# max3051_breadboard.net
KiCad netlist of a schematic drawn in EAGLE
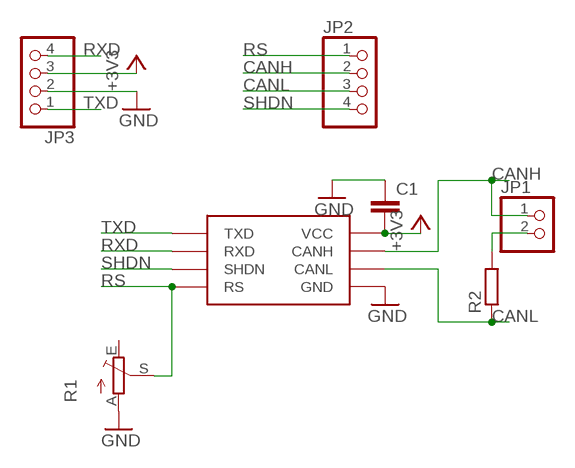
[diagram p0: schematic, sheet 1]

(export (version "E")
  (design (tool "Eeschema 10.0.6"))
  (components
    (comp (ref "C1")
      (value "C-EUC0603")
      (footprint "eagle-import:C0603")
      (libsource (lib "eagle-import") (part "C-EUC0603"))
    )
    (comp (ref "JP1")
      (value "PINHD-1X2")
      (footprint "eagle-import:1X02")
      (libsource (lib "eagle-import") (part "PINHD-1X2"))
    )
    (comp (ref "JP2")
      (value "PINHD-1X4")
      (footprint "eagle-import:1X04")
      (libsource (lib "eagle-import") (part "PINHD-1X4"))
    )
    (comp (ref "JP3")
      (value "PINHD-1X4")
      (footprint "eagle-import:1X04")
      (libsource (lib "eagle-import") (part "PINHD-1X4"))
    )
    (comp (ref "R1")
      (value "TRIM_EU-S64W")
      (footprint "eagle-import:S64W")
      (libsource (lib "eagle-import") (part "TRIM_EU-S64W"))
    )
    (comp (ref "R2")
      (value "R-EU_R0603")
      (footprint "eagle-import:R0603")
      (libsource (lib "eagle-import") (part "R-EU_R0603"))
    )
    (comp (ref "SOT1")
      (value "MAX3051ESA")
      (footprint "eagle-import:SO-08")
      (libsource (lib "eagle-import") (part "MAX3051ESA"))
    )
  )
  (nets
    (net (code "1") (name "+3V3") (class "Default")
      (node (ref "C1") (pin "2") (pinfunction "2_2") (pintype "passive"))
      (node (ref "JP3") (pin "3") (pinfunction "3_3") (pintype "passive"))
      (node (ref "SOT1") (pin "3") (pinfunction "VCC_3") (pintype "bidirectional"))
    )
    (net (code "2") (name "/CANH") (class "Default")
      (node (ref "JP1") (pin "1") (pinfunction "1_1") (pintype "passive"))
      (node (ref "JP2") (pin "2") (pinfunction "2_2") (pintype "passive"))
      (node (ref "SOT1") (pin "7") (pinfunction "CANH_7") (pintype "bidirectional"))
    )
    (net (code "3") (name "/CANL") (class "Default")
      (node (ref "JP2") (pin "3") (pinfunction "3_3") (pintype "passive"))
      (node (ref "R2") (pin "1") (pinfunction "1_1") (pintype "passive"))
      (node (ref "SOT1") (pin "6") (pinfunction "CANL_6") (pintype "bidirectional"))
    )
    (net (code "4") (name "/RS") (class "Default")
      (node (ref "JP2") (pin "1") (pinfunction "1_1") (pintype "passive"))
      (node (ref "R1") (pin "S") (pinfunction "S_S") (pintype "passive"))
      (node (ref "SOT1") (pin "8") (pinfunction "RS_8") (pintype "bidirectional"))
    )
    (net (code "5") (name "/RXD") (class "Default")
      (node (ref "JP3") (pin "4") (pinfunction "4_4") (pintype "passive"))
      (node (ref "SOT1") (pin "4") (pinfunction "RXD_4") (pintype "bidirectional"))
    )
    (net (code "6") (name "/SHDN") (class "Default")
      (node (ref "JP2") (pin "4") (pinfunction "4_4") (pintype "passive"))
      (node (ref "SOT1") (pin "5") (pinfunction "SHDN_5") (pintype "bidirectional"))
    )
    (net (code "7") (name "/TXD") (class "Default")
      (node (ref "JP3") (pin "1") (pinfunction "1_1") (pintype "passive"))
      (node (ref "SOT1") (pin "1") (pinfunction "TXD_1") (pintype "bidirectional"))
    )
    (net (code "8") (name "GND") (class "Default")
      (node (ref "C1") (pin "1") (pinfunction "1_1") (pintype "passive"))
      (node (ref "JP3") (pin "2") (pinfunction "2_2") (pintype "passive"))
      (node (ref "R1") (pin "A") (pinfunction "A_A") (pintype "passive"))
      (node (ref "SOT1") (pin "2") (pinfunction "GND_2") (pintype "bidirectional"))
    )
    (net (code "9") (name "Net-(JP1-Pad2)") (class "Default")
      (node (ref "JP1") (pin "2") (pinfunction "2_2") (pintype "passive"))
      (node (ref "R2") (pin "2") (pinfunction "2_2") (pintype "passive"))
    )
    (net (code "10") (name "unconnected-(R1-PadE)") (class "Default")
      (node (ref "R1") (pin "E") (pinfunction "E_E") (pintype "passive"))
    )
  )
)
